# RS232Converter.net
KiCad netlist of a schematic drawn in EAGLE
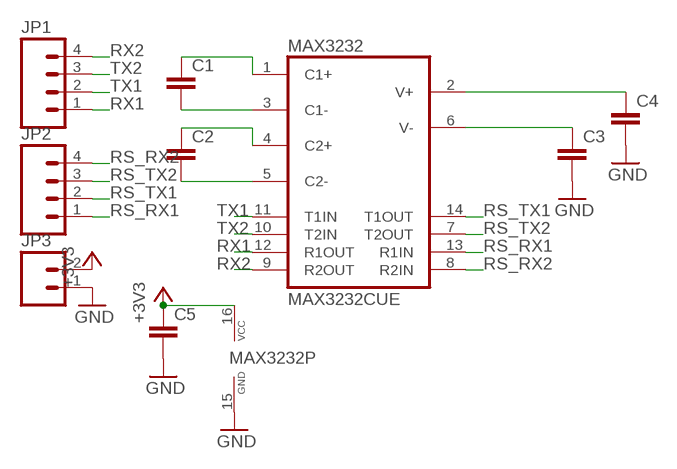
[diagram p0: schematic, sheet 1]

(export (version "E")
  (design (tool "Eeschema 10.0.6"))
  (components
    (comp (ref "C1")
      (value "CAP0603-CAP")
      (footprint "eagle-import:0603-CAP")
      (libsource (lib "eagle-import") (part "CAP0603-CAP"))
    )
    (comp (ref "C2")
      (value "CAP0603-CAP")
      (footprint "eagle-import:0603-CAP")
      (libsource (lib "eagle-import") (part "CAP0603-CAP"))
    )
    (comp (ref "C3")
      (value "CAP0603-CAP")
      (footprint "eagle-import:0603-CAP")
      (libsource (lib "eagle-import") (part "CAP0603-CAP"))
    )
    (comp (ref "C4")
      (value "CAP0603-CAP")
      (footprint "eagle-import:0603-CAP")
      (libsource (lib "eagle-import") (part "CAP0603-CAP"))
    )
    (comp (ref "C5")
      (value "CAP0603-CAP")
      (footprint "eagle-import:0603-CAP")
      (libsource (lib "eagle-import") (part "CAP0603-CAP"))
    )
    (comp (ref "JP1")
      (value "M04PTH")
      (footprint "eagle-import:1X04")
      (libsource (lib "eagle-import") (part "M04PTH"))
    )
    (comp (ref "JP2")
      (value "M04PTH")
      (footprint "eagle-import:1X04")
      (libsource (lib "eagle-import") (part "M04PTH"))
    )
    (comp (ref "JP3")
      (value "M02PTH")
      (footprint "eagle-import:1X02")
      (libsource (lib "eagle-import") (part "M02PTH"))
    )
    (comp (ref "MAX3232")
      (value "MAX3232CUE")
      (footprint "eagle-import:TSSOP16")
      (fields (field (name "MF") "MAXIM") (field (name "MPN") "MAX3232CUE+"))
      (libsource (lib "eagle-import") (part "MAX3232UEC"))
    )
  )
  (nets
    (net (code "1") (name "+3V3") (class "Default")
      (node (ref "C5") (pin "1") (pinfunction "1_1") (pintype "passive"))
      (node (ref "JP3") (pin "2") (pinfunction "2_2") (pintype "passive"))
      (node (ref "MAX3232") (pin "16") (pinfunction "VCC_16") (pintype "power_in"))
    )
    (net (code "2") (name "/RS_RX1") (class "Default")
      (node (ref "JP2") (pin "1") (pinfunction "1_1") (pintype "passive"))
      (node (ref "MAX3232") (pin "13") (pinfunction "R1IN_13") (pintype "input"))
    )
    (net (code "3") (name "/RS_RX2") (class "Default")
      (node (ref "JP2") (pin "4") (pinfunction "4_4") (pintype "passive"))
      (node (ref "MAX3232") (pin "8") (pinfunction "R2IN_8") (pintype "input"))
    )
    (net (code "4") (name "/RS_TX1") (class "Default")
      (node (ref "JP2") (pin "2") (pinfunction "2_2") (pintype "passive"))
      (node (ref "MAX3232") (pin "14") (pinfunction "T1OUT_14") (pintype "output"))
    )
    (net (code "5") (name "/RS_TX2") (class "Default")
      (node (ref "JP2") (pin "3") (pinfunction "3_3") (pintype "passive"))
      (node (ref "MAX3232") (pin "7") (pinfunction "T2OUT_7") (pintype "output"))
    )
    (net (code "6") (name "/RX1") (class "Default")
      (node (ref "JP1") (pin "1") (pinfunction "1_1") (pintype "passive"))
      (node (ref "MAX3232") (pin "12") (pinfunction "R1OUT_12") (pintype "output"))
    )
    (net (code "7") (name "/RX2") (class "Default")
      (node (ref "JP1") (pin "4") (pinfunction "4_4") (pintype "passive"))
      (node (ref "MAX3232") (pin "9") (pinfunction "R2OUT_9") (pintype "output"))
    )
    (net (code "8") (name "/TX1") (class "Default")
      (node (ref "JP1") (pin "2") (pinfunction "2_2") (pintype "passive"))
      (node (ref "MAX3232") (pin "11") (pinfunction "T1IN_11") (pintype "input"))
    )
    (net (code "9") (name "/TX2") (class "Default")
      (node (ref "JP1") (pin "3") (pinfunction "3_3") (pintype "passive"))
      (node (ref "MAX3232") (pin "10") (pinfunction "T2IN_10") (pintype "input"))
    )
    (net (code "10") (name "GND") (class "Default")
      (node (ref "C3") (pin "2") (pinfunction "2_2") (pintype "passive"))
      (node (ref "C4") (pin "2") (pinfunction "2_2") (pintype "passive"))
      (node (ref "C5") (pin "2") (pinfunction "2_2") (pintype "passive"))
      (node (ref "JP3") (pin "1") (pinfunction "1_1") (pintype "passive"))
      (node (ref "MAX3232") (pin "15") (pinfunction "GND_15") (pintype "power_in"))
    )
    (net (code "11") (name "Net-(MAX3232A-C1+)") (class "Default")
      (node (ref "C1") (pin "1") (pinfunction "1_1") (pintype "passive"))
      (node (ref "MAX3232") (pin "1") (pinfunction "C1+_1") (pintype "bidirectional"))
    )
    (net (code "12") (name "Net-(MAX3232A-C1-)") (class "Default")
      (node (ref "C1") (pin "2") (pinfunction "2_2") (pintype "passive"))
      (node (ref "MAX3232") (pin "3") (pinfunction "C1-_3") (pintype "bidirectional"))
    )
    (net (code "13") (name "Net-(MAX3232A-C2+)") (class "Default")
      (node (ref "C2") (pin "1") (pinfunction "1_1") (pintype "passive"))
      (node (ref "MAX3232") (pin "4") (pinfunction "C2+_4") (pintype "bidirectional"))
    )
    (net (code "14") (name "Net-(MAX3232A-C2-)") (class "Default")
      (node (ref "C2") (pin "2") (pinfunction "2_2") (pintype "passive"))
      (node (ref "MAX3232") (pin "5") (pinfunction "C2-_5") (pintype "bidirectional"))
    )
    (net (code "15") (name "Net-(MAX3232A-V+)") (class "Default")
      (node (ref "C4") (pin "1") (pinfunction "1_1") (pintype "passive"))
      (node (ref "MAX3232") (pin "2") (pinfunction "V+_2") (pintype "bidirectional"))
    )
    (net (code "16") (name "Net-(MAX3232A-V-)") (class "Default")
      (node (ref "C3") (pin "1") (pinfunction "1_1") (pintype "passive"))
      (node (ref "MAX3232") (pin "6") (pinfunction "V-_6") (pintype "bidirectional"))
    )
  )
)
